# cerebro5_1.net
KiCad netlist of a schematic drawn in EAGLE
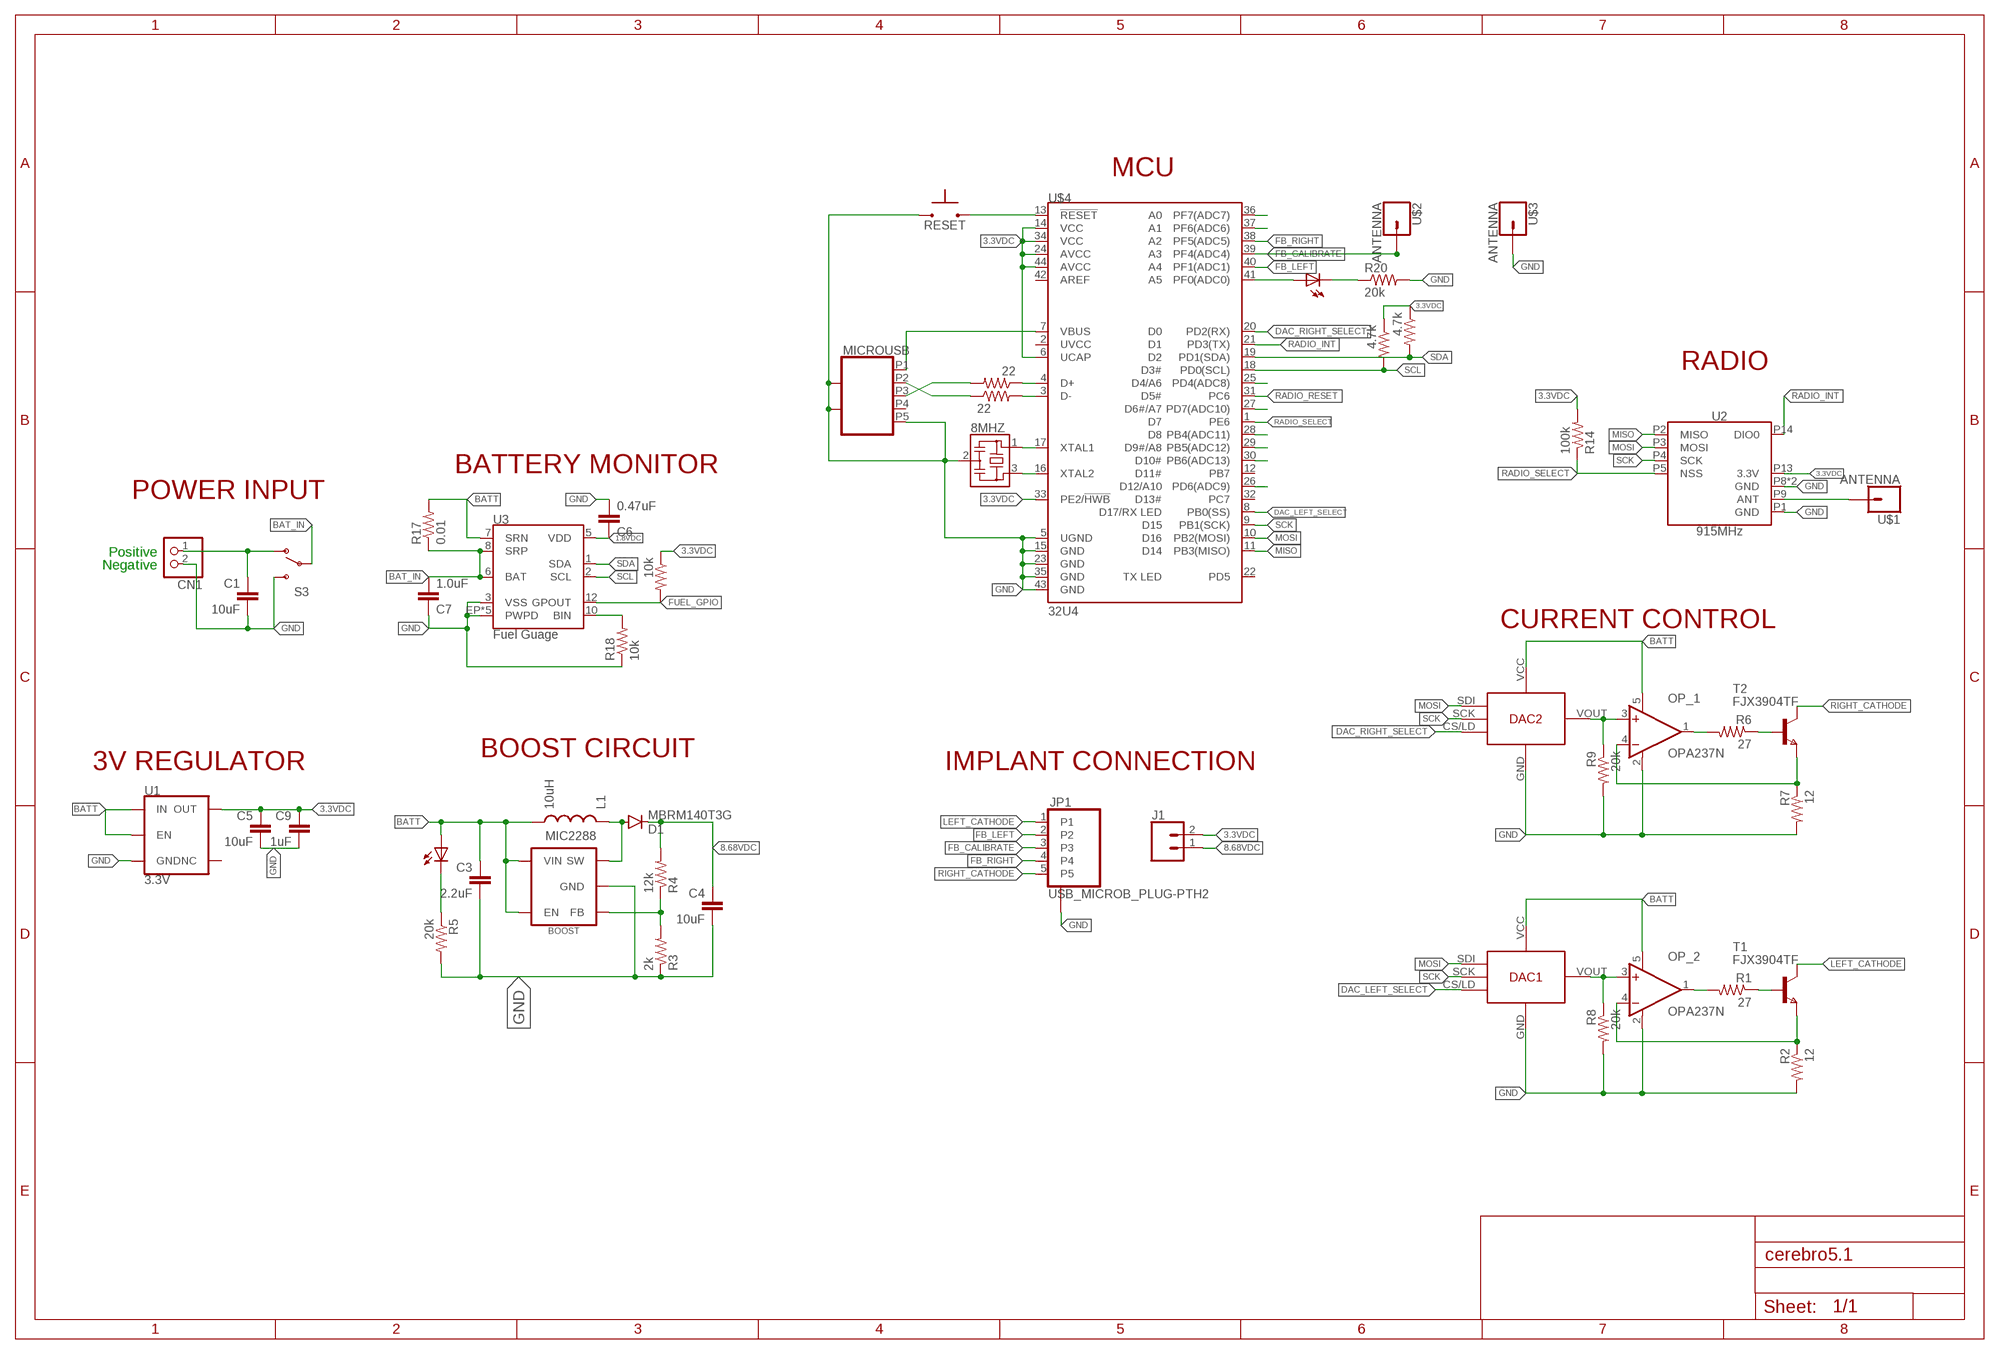
[diagram p0: schematic, sheet 1]

(export (version "E")
  (design (tool "Eeschema 10.0.6"))
  (components
    (comp (ref "8MHZ")
      (value "RESONATOR_CSTCE_V")
      (footprint "eagle-import:CSTCE_V")
      (libsource (lib "eagle-import") (part "RESONATOR_CSTCE_V"))
    )
    (comp (ref "C1")
      (value "10uF")
      (footprint "eagle-import:0805")
      (libsource (lib "eagle-import") (part "10UF-0805-10V-10%"))
    )
    (comp (ref "C3")
      (value "2.2uF")
      (footprint "eagle-import:0805")
      (libsource (lib "eagle-import") (part "2.2UF-0805-25V-(+80/-20%)"))
    )
    (comp (ref "C4")
      (value "10uF")
      (footprint "eagle-import:0805")
      (libsource (lib "eagle-import") (part "10UF-0805-10V-10%"))
    )
    (comp (ref "C5")
      (value "10uF")
      (footprint "eagle-import:0805")
      (libsource (lib "eagle-import") (part "10UF-0805-10V-10%"))
    )
    (comp (ref "C6")
      (value "0.47uF")
      (footprint "eagle-import:0805")
      (libsource (lib "eagle-import") (part "10UF-0805-10V-10%"))
    )
    (comp (ref "C7")
      (value "1.0uF")
      (footprint "eagle-import:0805")
      (libsource (lib "eagle-import") (part "10UF-0805-10V-10%"))
    )
    (comp (ref "C9")
      (value "1uF")
      (footprint "eagle-import:0805")
      (libsource (lib "eagle-import") (part "10UF-0805-10V-10%"))
    )
    (comp (ref "CN1")
      (value "JST_2PIN-SMT-RA")
      (footprint "eagle-import:JST-PH-2-SMT-RA")
      (libsource (lib "eagle-import") (part "JST_2PIN-SMT-RA"))
    )
    (comp (ref "D1")
      (value "MBRM140T3G")
      (footprint "eagle-import:POWERMITE")
      (libsource (lib "eagle-import") (part "DIODEPOWERMITE"))
    )
    (comp (ref "DAC1")
      (value "DAC_LTC2630")
      (footprint "eagle-import:SC-70")
      (libsource (lib "eagle-import") (part "DAC_LTC2630"))
    )
    (comp (ref "DAC2")
      (value "DAC_LTC2630")
      (footprint "eagle-import:SC-70")
      (libsource (lib "eagle-import") (part "DAC_LTC2630"))
    )
    (comp (ref "INDICATOR_LED")
      (value "LED")
      (footprint "eagle-import:CHIP-LED0603")
      (libsource (lib "eagle-import") (part "LEDCHIP-LED0603"))
    )
    (comp (ref "INDICATOR_LED1")
      (value "LED")
      (footprint "eagle-import:CHIP-LED0603")
      (libsource (lib "eagle-import") (part "LEDCHIP-LED0603"))
    )
    (comp (ref "J1")
      (value "CONN_02")
      (footprint "eagle-import:1X02")
      (libsource (lib "eagle-import") (part "CONN_02"))
    )
    (comp (ref "JP1")
      (value "USB_MICROB_PLUG-PTH2")
      (footprint "eagle-import:MICRO-B-TH")
      (libsource (lib "eagle-import") (part "USB_MICROB_PLUG-PTH2"))
    )
    (comp (ref "L1")
      (value "10uH")
      (footprint "eagle-import:1812")
      (libsource (lib "eagle-import") (part "INDUCTORLQH4"))
    )
    (comp (ref "MIC2288")
      (value "BOOST")
      (footprint "eagle-import:SOT23-5")
      (libsource (lib "eagle-import") (part "BOOST_CONVERTER"))
    )
    (comp (ref "MICROUSB")
      (value "USB_MICRO_SOCKET_HORZ_REINFORCED")
      (footprint "eagle-import:USB_HORZ_REINFORCED_MICRO")
      (libsource (lib "eagle-import") (part "USB_MICRO_SOCKET_HORZ_REINFORCED"))
    )
    (comp (ref "OP_1")
      (value "OPA237N")
      (footprint "eagle-import:SOT23-5")
      (fields (field (name "MF") "TEXAS INSTRUMENTS") (field (name "MPN") "OPA237NA/250"))
      (libsource (lib "eagle-import") (part "OPA237N"))
    )
    (comp (ref "OP_2")
      (value "OPA237N")
      (footprint "eagle-import:SOT23-5")
      (fields (field (name "MF") "TEXAS INSTRUMENTS") (field (name "MPN") "OPA237NA/250"))
      (libsource (lib "eagle-import") (part "OPA237N"))
    )
    (comp (ref "R1")
      (value "27")
      (footprint "eagle-import:0603-RES")
      (libsource (lib "eagle-import") (part "RESISTOR0603-RES"))
    )
    (comp (ref "R2")
      (value "12")
      (footprint "eagle-import:0603-RES")
      (libsource (lib "eagle-import") (part "RESISTOR0603-RES"))
    )
    (comp (ref "R3")
      (value "2k")
      (footprint "eagle-import:0603-RES")
      (libsource (lib "eagle-import") (part "RESISTOR0603-RES"))
    )
    (comp (ref "R4")
      (value "12k")
      (footprint "eagle-import:0805")
      (libsource (lib "eagle-import") (part "RESISTOR0805-RES"))
    )
    (comp (ref "R5")
      (value "20k")
      (footprint "eagle-import:0603-RES")
      (libsource (lib "eagle-import") (part "RESISTOR0603-RES"))
    )
    (comp (ref "R6")
      (value "27")
      (footprint "eagle-import:0603-RES")
      (libsource (lib "eagle-import") (part "RESISTOR0603-RES"))
    )
    (comp (ref "R7")
      (value "12")
      (footprint "eagle-import:0603-RES")
      (libsource (lib "eagle-import") (part "RESISTOR0603-RES"))
    )
    (comp (ref "R8")
      (value "20k")
      (footprint "eagle-import:0603-RES")
      (libsource (lib "eagle-import") (part "RESISTOR0603-RES"))
    )
    (comp (ref "R9")
      (value "20k")
      (footprint "eagle-import:0603-RES")
      (libsource (lib "eagle-import") (part "RESISTOR0603-RES"))
    )
    (comp (ref "R12")
      (value "22")
      (footprint "eagle-import:0603-RES")
      (libsource (lib "eagle-import") (part "RESISTOR0603-RES"))
    )
    (comp (ref "R13")
      (value "22")
      (footprint "eagle-import:0603-RES")
      (libsource (lib "eagle-import") (part "RESISTOR0603-RES"))
    )
    (comp (ref "R14")
      (value "100k")
      (footprint "eagle-import:0603-RES")
      (libsource (lib "eagle-import") (part "RESISTOR0603-RES"))
    )
    (comp (ref "R15")
      (value "4.7k")
      (footprint "eagle-import:0603-RES")
      (libsource (lib "eagle-import") (part "RESISTOR0603-RES"))
    )
    (comp (ref "R16")
      (value "4.7k")
      (footprint "eagle-import:0603-RES")
      (libsource (lib "eagle-import") (part "RESISTOR0603-RES"))
    )
    (comp (ref "R17")
      (value "0.01")
      (footprint "eagle-import:1206")
      (libsource (lib "eagle-import") (part "RESISTOR1206"))
    )
    (comp (ref "R18")
      (value "10k")
      (footprint "eagle-import:0603-RES")
      (libsource (lib "eagle-import") (part "RESISTOR0603-RES"))
    )
    (comp (ref "R19")
      (value "10k")
      (footprint "eagle-import:0603-RES")
      (libsource (lib "eagle-import") (part "RESISTOR0603-RES"))
    )
    (comp (ref "R20")
      (value "20k")
      (footprint "eagle-import:0603-RES")
      (libsource (lib "eagle-import") (part "RESISTOR0603-RES"))
    )
    (comp (ref "RESET")
      (value "SWITCH-MOMENTARY-NO")
      (footprint "eagle-import:SWITCH_MOMENTARY_XS")
      (libsource (lib "eagle-import") (part "SWITCH-MOMENTARY-NO"))
    )
    (comp (ref "S3")
      (value "SWITCH-SPDTSMD2")
      (footprint "eagle-import:SWITCH-SPDT-SMD")
      (libsource (lib "eagle-import") (part "SWITCH-SPDTSMD2"))
    )
    (comp (ref "T1")
      (value "FJX3904TF")
      (footprint "eagle-import:SOT323")
      (fields (field (name "MPN") "DSS4160U-7"))
      (libsource (lib "eagle-import") (part "NPNSOT323"))
    )
    (comp (ref "T2")
      (value "FJX3904TF")
      (footprint "eagle-import:SOT323")
      (fields (field (name "MPN") "DSS4160U-7"))
      (libsource (lib "eagle-import") (part "NPNSOT323"))
    )
    (comp (ref "U$1")
      (value "ANTENNA")
      (footprint "eagle-import:1X01")
      (libsource (lib "eagle-import") (part "ANTENNA"))
    )
    (comp (ref "U$2")
      (value "ANTENNA")
      (footprint "eagle-import:1X01")
      (libsource (lib "eagle-import") (part "ANTENNA"))
    )
    (comp (ref "U$3")
      (value "ANTENNA")
      (footprint "eagle-import:1X01")
      (libsource (lib "eagle-import") (part "ANTENNA"))
    )
    (comp (ref "U$4")
      (value "32U4")
      (footprint "eagle-import:QFN-44-NOPAD")
      (libsource (lib "eagle-import") (part "ATMEGA32U4QFN2"))
    )
    (comp (ref "U1")
      (value "3.3V")
      (footprint "eagle-import:SOT23-5")
      (libsource (lib "eagle-import") (part "V_REG_AP2112K-3.3V"))
    )
    (comp (ref "U2")
      (value "915MHz")
      (footprint "eagle-import:RFM69HCW-XXXS2")
      (libsource (lib "eagle-import") (part "RFM69HCW-915"))
    )
    (comp (ref "U3")
      (value "Fuel Guage")
      (footprint "eagle-import:PDSO-N12")
      (libsource (lib "eagle-import") (part "BQ27441-G1"))
    )
  )
  (nets
    (net (code "1") (name "1.8VDC") (class "Default")
      (node (ref "C6") (pin "1") (pinfunction "1_1") (pintype "passive"))
      (node (ref "U3") (pin "5") (pinfunction "VDD_5") (pintype "bidirectional"))
    )
    (net (code "2") (name "3.3VDC") (class "Default")
      (node (ref "C5") (pin "1") (pinfunction "1_1") (pintype "passive"))
      (node (ref "C9") (pin "1") (pinfunction "1_1") (pintype "passive"))
      (node (ref "J1") (pin "2") (pinfunction "2_2") (pintype "passive"))
      (node (ref "R14") (pin "2") (pinfunction "2_2") (pintype "passive"))
      (node (ref "R15") (pin "1") (pinfunction "1_1") (pintype "passive"))
      (node (ref "R16") (pin "1") (pinfunction "1_1") (pintype "passive"))
      (node (ref "R19") (pin "1") (pinfunction "1_1") (pintype "passive"))
      (node (ref "U$4") (pin "14") (pinfunction "VCC_14") (pintype "bidirectional"))
      (node (ref "U$4") (pin "24") (pinfunction "AVCC_24") (pintype "bidirectional"))
      (node (ref "U$4") (pin "33") (pinfunction "PE2/~{HWB}_33") (pintype "bidirectional"))
      (node (ref "U$4") (pin "34") (pinfunction "VCC_34") (pintype "bidirectional"))
      (node (ref "U$4") (pin "44") (pinfunction "AVCC_44") (pintype "bidirectional"))
      (node (ref "U$4") (pin "6") (pinfunction "UCAP_6") (pintype "bidirectional"))
      (node (ref "U1") (pin "5") (pinfunction "OUT_5") (pintype "passive"))
      (node (ref "U2") (pin "P13") (pinfunction "3.3V_P13") (pintype "power_in"))
    )
    (net (code "3") (name "8.68VDC") (class "Default")
      (node (ref "C4") (pin "1") (pinfunction "1_1") (pintype "passive"))
      (node (ref "D1") (pin "CATHODE") (pinfunction "C_CATHODE") (pintype "passive"))
      (node (ref "J1") (pin "1") (pinfunction "1_1") (pintype "passive"))
      (node (ref "R4") (pin "2") (pinfunction "2_2") (pintype "passive"))
    )
    (net (code "4") (name "BATT") (class "Default")
      (node (ref "C3") (pin "1") (pinfunction "1_1") (pintype "passive"))
      (node (ref "DAC1") (pin "VCC") (pinfunction "VIN_VCC") (pintype "bidirectional"))
      (node (ref "DAC2") (pin "VCC") (pinfunction "VIN_VCC") (pintype "bidirectional"))
      (node (ref "INDICATOR_LED") (pin "A") (pinfunction "A_A") (pintype "passive"))
      (node (ref "L1") (pin "P$2") (pinfunction "2_P$2") (pintype "passive"))
      (node (ref "L1") (pin "P$4") (pinfunction "2_P$4") (pintype "passive"))
      (node (ref "MIC2288") (pin "4") (pinfunction "EN_4") (pintype "input"))
      (node (ref "MIC2288") (pin "5") (pinfunction "VIN_5") (pintype "passive"))
      (node (ref "OP_1") (pin "5") (pinfunction "V+_5") (pintype "power_in"))
      (node (ref "OP_2") (pin "5") (pinfunction "V+_5") (pintype "power_in"))
      (node (ref "R17") (pin "2") (pinfunction "2_2") (pintype "passive"))
      (node (ref "U1") (pin "1") (pinfunction "IN_1") (pintype "input"))
      (node (ref "U1") (pin "3") (pinfunction "EN_3") (pintype "input"))
      (node (ref "U3") (pin "7") (pinfunction "SRN_7") (pintype "bidirectional"))
    )
    (net (code "5") (name "BAT_IN") (class "Default")
      (node (ref "C7") (pin "2") (pinfunction "2_2") (pintype "passive"))
      (node (ref "R17") (pin "1") (pinfunction "1_1") (pintype "passive"))
      (node (ref "S3") (pin "2") (pinfunction "P_2") (pintype "passive"))
      (node (ref "U3") (pin "6") (pinfunction "BAT_6") (pintype "bidirectional"))
      (node (ref "U3") (pin "8") (pinfunction "SRP_8") (pintype "bidirectional"))
    )
    (net (code "6") (name "DAC_LEFT_SELECT") (class "Default")
      (node (ref "DAC1") (pin "CS/LD") (pinfunction "CS/LD_CS/LD") (pintype "bidirectional"))
      (node (ref "U$4") (pin "8") (pinfunction "PB0(SS)_8") (pintype "bidirectional"))
    )
    (net (code "7") (name "DAC_RIGHT_SELECT") (class "Default")
      (node (ref "DAC2") (pin "CS/LD") (pinfunction "CS/LD_CS/LD") (pintype "bidirectional"))
      (node (ref "U$4") (pin "20") (pinfunction "PD2(RX)_20") (pintype "bidirectional"))
    )
    (net (code "8") (name "FB_CALIBRATE") (class "Default")
      (node (ref "JP1") (pin "3") (pinfunction "P3_3") (pintype "bidirectional"))
      (node (ref "U$2") (pin "1") (pinfunction "1_1") (pintype "passive"))
      (node (ref "U$4") (pin "39") (pinfunction "PF4(ADC4)_39") (pintype "bidirectional"))
    )
    (net (code "9") (name "FB_LEFT") (class "Default")
      (node (ref "JP1") (pin "2") (pinfunction "P2_2") (pintype "bidirectional"))
      (node (ref "U$4") (pin "40") (pinfunction "PF1(ADC1)_40") (pintype "bidirectional"))
    )
    (net (code "10") (name "FB_RIGHT") (class "Default")
      (node (ref "JP1") (pin "4") (pinfunction "P4_4") (pintype "bidirectional"))
      (node (ref "U$4") (pin "38") (pinfunction "PF5(ADC5)_38") (pintype "bidirectional"))
    )
    (net (code "11") (name "FUEL_GPIO") (class "Default")
      (node (ref "R19") (pin "2") (pinfunction "2_2") (pintype "passive"))
      (node (ref "U3") (pin "12") (pinfunction "GPOUT_12") (pintype "bidirectional"))
    )
    (net (code "12") (name "GND") (class "Default")
      (node (ref "8MHZ") (pin "2") (pinfunction "2_2") (pintype "passive"))
      (node (ref "C1") (pin "2") (pinfunction "2_2") (pintype "passive"))
      (node (ref "C3") (pin "2") (pinfunction "2_2") (pintype "passive"))
      (node (ref "C4") (pin "2") (pinfunction "2_2") (pintype "passive"))
      (node (ref "C5") (pin "2") (pinfunction "2_2") (pintype "passive"))
      (node (ref "C6") (pin "2") (pinfunction "2_2") (pintype "passive"))
      (node (ref "C7") (pin "1") (pinfunction "1_1") (pintype "passive"))
      (node (ref "C9") (pin "2") (pinfunction "2_2") (pintype "passive"))
      (node (ref "CN1") (pin "2") (pinfunction "1_2") (pintype "passive"))
      (node (ref "DAC1") (pin "GND") (pinfunction "GND_GND") (pintype "bidirectional"))
      (node (ref "DAC2") (pin "GND") (pinfunction "GND_GND") (pintype "bidirectional"))
      (node (ref "JP1") (pin "P$1") (pinfunction "GND_PINS_P$1") (pintype "bidirectional"))
      (node (ref "JP1") (pin "P$2") (pinfunction "GND_PINS_P$2") (pintype "bidirectional"))
      (node (ref "MIC2288") (pin "2") (pinfunction "GND_2") (pintype "input"))
      (node (ref "MICROUSB") (pin "G1") (pinfunction "P$1_G1") (pintype "bidirectional"))
      (node (ref "MICROUSB") (pin "G2") (pinfunction "P$1_G2") (pintype "bidirectional"))
      (node (ref "MICROUSB") (pin "P$1") (pinfunction "P$2_P$1") (pintype "bidirectional"))
      (node (ref "MICROUSB") (pin "P$2") (pinfunction "P$2_P$2") (pintype "bidirectional"))
      (node (ref "MICROUSB") (pin "P5") (pinfunction "P5_P5") (pintype "bidirectional"))
      (node (ref "OP_1") (pin "2") (pinfunction "V-_2") (pintype "power_in"))
      (node (ref "OP_2") (pin "2") (pinfunction "V-_2") (pintype "power_in"))
      (node (ref "R18") (pin "1") (pinfunction "1_1") (pintype "passive"))
      (node (ref "R2") (pin "2") (pinfunction "2_2") (pintype "passive"))
      (node (ref "R20") (pin "2") (pinfunction "2_2") (pintype "passive"))
      (node (ref "R3") (pin "1") (pinfunction "1_1") (pintype "passive"))
      (node (ref "R5") (pin "2") (pinfunction "2_2") (pintype "passive"))
      (node (ref "R7") (pin "2") (pinfunction "2_2") (pintype "passive"))
      (node (ref "R8") (pin "2") (pinfunction "2_2") (pintype "passive"))
      (node (ref "R9") (pin "2") (pinfunction "2_2") (pintype "passive"))
      (node (ref "RESET") (pin "P$1") (pinfunction "1_P$1") (pintype "bidirectional"))
      (node (ref "S3") (pin "3") (pinfunction "S_3") (pintype "passive"))
      (node (ref "U$3") (pin "1") (pinfunction "1_1") (pintype "passive"))
      (node (ref "U$4") (pin "15") (pinfunction "GND_15") (pintype "bidirectional"))
      (node (ref "U$4") (pin "23") (pinfunction "GND_23") (pintype "bidirectional"))
      (node (ref "U$4") (pin "35") (pinfunction "GND_35") (pintype "bidirectional"))
      (node (ref "U$4") (pin "43") (pinfunction "GND_43") (pintype "bidirectional"))
      (node (ref "U$4") (pin "5") (pinfunction "UGND_5") (pintype "bidirectional"))
      (node (ref "U1") (pin "2") (pinfunction "GND_2") (pintype "input"))
      (node (ref "U2") (pin "P1") (pinfunction "GND_P1") (pintype "power_in"))
      (node (ref "U2") (pin "P10") (pinfunction "GND_P10") (pintype "power_in"))
      (node (ref "U2") (pin "P8") (pinfunction "GND_P8") (pintype "power_in"))
      (node (ref "U3") (pin "3") (pinfunction "VSS_3") (pintype "bidirectional"))
      (node (ref "U3") (pin "EP") (pinfunction "PWPD_EP") (pintype "bidirectional"))
      (node (ref "U3") (pin "EP1") (pinfunction "PWPD_EP1") (pintype "bidirectional"))
      (node (ref "U3") (pin "EP2") (pinfunction "PWPD_EP2") (pintype "bidirectional"))
      (node (ref "U3") (pin "EP3") (pinfunction "PWPD_EP3") (pintype "bidirectional"))
      (node (ref "U3") (pin "EP4") (pinfunction "PWPD_EP4") (pintype "bidirectional"))
    )
    (net (code "13") (name "LEFT_CATHODE") (class "Default")
      (node (ref "JP1") (pin "1") (pinfunction "P1_1") (pintype "bidirectional"))
      (node (ref "T1") (pin "1") (pinfunction "C_1") (pintype "passive"))
    )
    (net (code "14") (name "MISO") (class "Default")
      (node (ref "U$4") (pin "11") (pinfunction "PB3(MISO)_11") (pintype "bidirectional"))
      (node (ref "U2") (pin "P2") (pinfunction "MISO_P2") (pintype "bidirectional"))
    )
    (net (code "15") (name "MOSI") (class "Default")
      (node (ref "DAC1") (pin "SDI") (pinfunction "SDI_SDI") (pintype "bidirectional"))
      (node (ref "DAC2") (pin "SDI") (pinfunction "SDI_SDI") (pintype "bidirectional"))
      (node (ref "U$4") (pin "10") (pinfunction "PB2(MOSI)_10") (pintype "bidirectional"))
      (node (ref "U2") (pin "P3") (pinfunction "MOSI_P3") (pintype "input"))
    )
    (net (code "16") (name "Net-(CN1-2)") (class "Default")
      (node (ref "C1") (pin "1") (pinfunction "1_1") (pintype "passive"))
      (node (ref "CN1") (pin "1") (pinfunction "2_1") (pintype "passive"))
      (node (ref "S3") (pin "1") (pinfunction "O_1") (pintype "passive"))
    )
    (net (code "17") (name "Net-(D1-A)") (class "Default")
      (node (ref "D1") (pin "ANODE") (pinfunction "A_ANODE") (pintype "passive"))
      (node (ref "L1") (pin "P$1") (pinfunction "1_P$1") (pintype "passive"))
      (node (ref "L1") (pin "P$3") (pinfunction "1_P$3") (pintype "passive"))
      (node (ref "MIC2288") (pin "1") (pinfunction "SW_1") (pintype "input"))
    )
    (net (code "18") (name "Net-(INDICATOR_LED-PadC)") (class "Default")
      (node (ref "INDICATOR_LED") (pin "C") (pinfunction "C_C") (pintype "passive"))
      (node (ref "R5") (pin "1") (pinfunction "1_1") (pintype "passive"))
    )
    (net (code "19") (name "Net-(INDICATOR_LED1-PadC)") (class "Default")
      (node (ref "INDICATOR_LED1") (pin "C") (pinfunction "C_C") (pintype "passive"))
      (node (ref "R20") (pin "1") (pinfunction "1_1") (pintype "passive"))
    )
    (net (code "20") (name "Net-(MIC2288-FB)") (class "Default")
      (node (ref "MIC2288") (pin "3") (pinfunction "FB_3") (pintype "input"))
      (node (ref "R3") (pin "2") (pinfunction "2_2") (pintype "passive"))
      (node (ref "R4") (pin "1") (pinfunction "1_1") (pintype "passive"))
    )
    (net (code "21") (name "Net-(MICROUSB-PadP2)") (class "Default")
      (node (ref "MICROUSB") (pin "P2") (pinfunction "P2_P2") (pintype "bidirectional"))
      (node (ref "R13") (pin "1") (pinfunction "1_1") (pintype "passive"))
    )
    (net (code "22") (name "Net-(MICROUSB-PadP3)") (class "Default")
      (node (ref "MICROUSB") (pin "P3") (pinfunction "P3_P3") (pintype "bidirectional"))
      (node (ref "R12") (pin "2") (pinfunction "2_2") (pintype "passive"))
    )
    (net (code "23") (name "Net-(OP_1-+IN)") (class "Default")
      (node (ref "DAC2") (pin "VOUT") (pinfunction "VOUT_VOUT") (pintype "bidirectional"))
      (node (ref "OP_1") (pin "3") (pinfunction "+IN_3") (pintype "input"))
      (node (ref "R9") (pin "1") (pinfunction "1_1") (pintype "passive"))
    )
    (net (code "24") (name "Net-(OP_1--IN)") (class "Default")
      (node (ref "OP_1") (pin "4") (pinfunction "-IN_4") (pintype "input"))
      (node (ref "R7") (pin "1") (pinfunction "1_1") (pintype "passive"))
      (node (ref "T2") (pin "3") (pinfunction "E_3") (pintype "passive"))
    )
    (net (code "25") (name "Net-(OP_1-OUT)") (class "Default")
      (node (ref "OP_1") (pin "1") (pinfunction "OUT_1") (pintype "output"))
      (node (ref "R6") (pin "2") (pinfunction "2_2") (pintype "passive"))
    )
    (net (code "26") (name "Net-(OP_2-+IN)") (class "Default")
      (node (ref "DAC1") (pin "VOUT") (pinfunction "VOUT_VOUT") (pintype "bidirectional"))
      (node (ref "OP_2") (pin "3") (pinfunction "+IN_3") (pintype "input"))
      (node (ref "R8") (pin "1") (pinfunction "1_1") (pintype "passive"))
    )
    (net (code "27") (name "Net-(OP_2--IN)") (class "Default")
      (node (ref "OP_2") (pin "4") (pinfunction "-IN_4") (pintype "input"))
      (node (ref "R2") (pin "1") (pinfunction "1_1") (pintype "passive"))
      (node (ref "T1") (pin "3") (pinfunction "E_3") (pintype "passive"))
    )
    (net (code "28") (name "Net-(OP_2-OUT)") (class "Default")
      (node (ref "OP_2") (pin "1") (pinfunction "OUT_1") (pintype "output"))
      (node (ref "R1") (pin "2") (pinfunction "2_2") (pintype "passive"))
    )
    (net (code "29") (name "Net-(RESET-2)") (class "Default")
      (node (ref "RESET") (pin "P$2") (pinfunction "2_P$2") (pintype "bidirectional"))
      (node (ref "U$4") (pin "13") (pinfunction "~{RESET}_13") (pintype "bidirectional"))
    )
    (net (code "30") (name "Net-(T1-B)") (class "Default")
      (node (ref "R1") (pin "1") (pinfunction "1_1") (pintype "passive"))
      (node (ref "T1") (pin "2") (pinfunction "B_2") (pintype "passive"))
    )
    (net (code "31") (name "Net-(T2-B)") (class "Default")
      (node (ref "R6") (pin "1") (pinfunction "1_1") (pintype "passive"))
      (node (ref "T2") (pin "2") (pinfunction "B_2") (pintype "passive"))
    )
    (net (code "32") (name "Net-(U$4-D+)") (class "Default")
      (node (ref "R12") (pin "1") (pinfunction "1_1") (pintype "passive"))
      (node (ref "U$4") (pin "4") (pinfunction "D+_4") (pintype "bidirectional"))
    )
    (net (code "33") (name "Net-(U$4-D-)") (class "Default")
      (node (ref "R13") (pin "2") (pinfunction "2_2") (pintype "passive"))
      (node (ref "U$4") (pin "3") (pinfunction "D-_3") (pintype "bidirectional"))
    )
    (net (code "34") (name "Net-(U$4-PF0(ADC0))") (class "Default")
      (node (ref "INDICATOR_LED1") (pin "A") (pinfunction "A_A") (pintype "passive"))
      (node (ref "U$4") (pin "41") (pinfunction "PF0(ADC0)_41") (pintype "bidirectional"))
    )
    (net (code "35") (name "Net-(U$4-VBUS)") (class "Default")
      (node (ref "MICROUSB") (pin "P1") (pinfunction "P1_P1") (pintype "bidirectional"))
      (node (ref "U$4") (pin "7") (pinfunction "VBUS_7") (pintype "bidirectional"))
    )
    (net (code "36") (name "Net-(U$4-XTAL1)") (class "Default")
      (node (ref "8MHZ") (pin "1") (pinfunction "1_1") (pintype "passive"))
      (node (ref "U$4") (pin "17") (pinfunction "XTAL1_17") (pintype "bidirectional"))
    )
    (net (code "37") (name "Net-(U$4-XTAL2)") (class "Default")
      (node (ref "8MHZ") (pin "3") (pinfunction "3_3") (pintype "passive"))
      (node (ref "U$4") (pin "16") (pinfunction "XTAL2_16") (pintype "bidirectional"))
    )
    (net (code "38") (name "Net-(U2-ANT)") (class "Default")
      (node (ref "U$1") (pin "1") (pinfunction "1_1") (pintype "passive"))
      (node (ref "U2") (pin "P9") (pinfunction "ANT_P9") (pintype "passive"))
    )
    (net (code "39") (name "Net-(U3-BIN)") (class "Default")
      (node (ref "R18") (pin "2") (pinfunction "2_2") (pintype "passive"))
      (node (ref "U3") (pin "10") (pinfunction "BIN_10") (pintype "bidirectional"))
    )
    (net (code "40") (name "RADIO_INT") (class "Default")
      (node (ref "U$4") (pin "21") (pinfunction "PD3(TX)_21") (pintype "bidirectional"))
      (node (ref "U2") (pin "P14") (pinfunction "DIO0_P14") (pintype "bidirectional"))
    )
    (net (code "41") (name "RADIO_RESET") (class "Default")
      (node (ref "U$4") (pin "31") (pinfunction "PC6_31") (pintype "bidirectional"))
    )
    (net (code "42") (name "RADIO_SELECT") (class "Default")
      (node (ref "R14") (pin "1") (pinfunction "1_1") (pintype "passive"))
      (node (ref "U$4") (pin "1") (pinfunction "PE6_1") (pintype "bidirectional"))
      (node (ref "U2") (pin "P5") (pinfunction "NSS_P5") (pintype "input"))
    )
    (net (code "43") (name "RIGHT_CATHODE") (class "Default")
      (node (ref "JP1") (pin "5") (pinfunction "P5_5") (pintype "bidirectional"))
      (node (ref "T2") (pin "1") (pinfunction "C_1") (pintype "passive"))
    )
    (net (code "44") (name "SCK") (class "Default")
      (node (ref "DAC1") (pin "SCK") (pinfunction "SCK_SCK") (pintype "bidirectional"))
      (node (ref "DAC2") (pin "SCK") (pinfunction "SCK_SCK") (pintype "bidirectional"))
      (node (ref "U$4") (pin "9") (pinfunction "PB1(SCK)_9") (pintype "bidirectional"))
      (node (ref "U2") (pin "P4") (pinfunction "SCK_P4") (pintype "input"))
    )
    (net (code "45") (name "SCL") (class "Default")
      (node (ref "R15") (pin "2") (pinfunction "2_2") (pintype "passive"))
      (node (ref "U$4") (pin "18") (pinfunction "PD0(SCL)_18") (pintype "bidirectional"))
      (node (ref "U3") (pin "2") (pinfunction "SCL_2") (pintype "bidirectional"))
    )
    (net (code "46") (name "SDA") (class "Default")
      (node (ref "R16") (pin "2") (pinfunction "2_2") (pintype "passive"))
      (node (ref "U$4") (pin "19") (pinfunction "PD1(SDA)_19") (pintype "bidirectional"))
      (node (ref "U3") (pin "1") (pinfunction "SDA_1") (pintype "bidirectional"))
    )
    (net (code "47") (name "unconnected-(MICROUSB-PadP4)") (class "Default")
      (node (ref "MICROUSB") (pin "P4") (pinfunction "P4_P4") (pintype "bidirectional"))
    )
    (net (code "48") (name "unconnected-(U$4-AREF-Pad42)") (class "Default")
      (node (ref "U$4") (pin "42") (pinfunction "AREF_42") (pintype "bidirectional"))
    )
    (net (code "49") (name "unconnected-(U$4-PB4(ADC11)-Pad28)") (class "Default")
      (node (ref "U$4") (pin "28") (pinfunction "PB4(ADC11)_28") (pintype "bidirectional"))
    )
    (net (code "50") (name "unconnected-(U$4-PB5(ADC12)-Pad29)") (class "Default")
      (node (ref "U$4") (pin "29") (pinfunction "PB5(ADC12)_29") (pintype "bidirectional"))
    )
    (net (code "51") (name "unconnected-(U$4-PB6(ADC13)-Pad30)") (class "Default")
      (node (ref "U$4") (pin "30") (pinfunction "PB6(ADC13)_30") (pintype "bidirectional"))
    )
    (net (code "52") (name "unconnected-(U$4-PB7-Pad12)") (class "Default")
      (node (ref "U$4") (pin "12") (pinfunction "PB7_12") (pintype "bidirectional"))
    )
    (net (code "53") (name "unconnected-(U$4-PC7-Pad32)") (class "Default")
      (node (ref "U$4") (pin "32") (pinfunction "PC7_32") (pintype "bidirectional"))
    )
    (net (code "54") (name "unconnected-(U$4-PD4(ADC8)-Pad25)") (class "Default")
      (node (ref "U$4") (pin "25") (pinfunction "PD4(ADC8)_25") (pintype "bidirectional"))
    )
    (net (code "55") (name "unconnected-(U$4-PD5-Pad22)") (class "Default")
      (node (ref "U$4") (pin "22") (pinfunction "PD5_22") (pintype "bidirectional"))
    )
    (net (code "56") (name "unconnected-(U$4-PD6(ADC9)-Pad26)") (class "Default")
      (node (ref "U$4") (pin "26") (pinfunction "PD6(ADC9)_26") (pintype "bidirectional"))
    )
    (net (code "57") (name "unconnected-(U$4-PD7(ADC10)-Pad27)") (class "Default")
      (node (ref "U$4") (pin "27") (pinfunction "PD7(ADC10)_27") (pintype "bidirectional"))
    )
    (net (code "58") (name "unconnected-(U$4-PF6(ADC6)-Pad37)") (class "Default")
      (node (ref "U$4") (pin "37") (pinfunction "PF6(ADC6)_37") (pintype "bidirectional"))
    )
    (net (code "59") (name "unconnected-(U$4-PF7(ADC7)-Pad36)") (class "Default")
      (node (ref "U$4") (pin "36") (pinfunction "PF7(ADC7)_36") (pintype "bidirectional"))
    )
    (net (code "60") (name "unconnected-(U$4-UVCC-Pad2)") (class "Default")
      (node (ref "U$4") (pin "2") (pinfunction "UVCC_2") (pintype "bidirectional"))
    )
    (net (code "61") (name "unconnected-(U1-NC-Pad4)") (class "Default")
      (node (ref "U1") (pin "4") (pinfunction "NC_4") (pintype "no_connect"))
    )
  )
)
